# SCH_directMessage_2022-07-24.net
KiCad netlist of a schematic drawn in EasyEDA
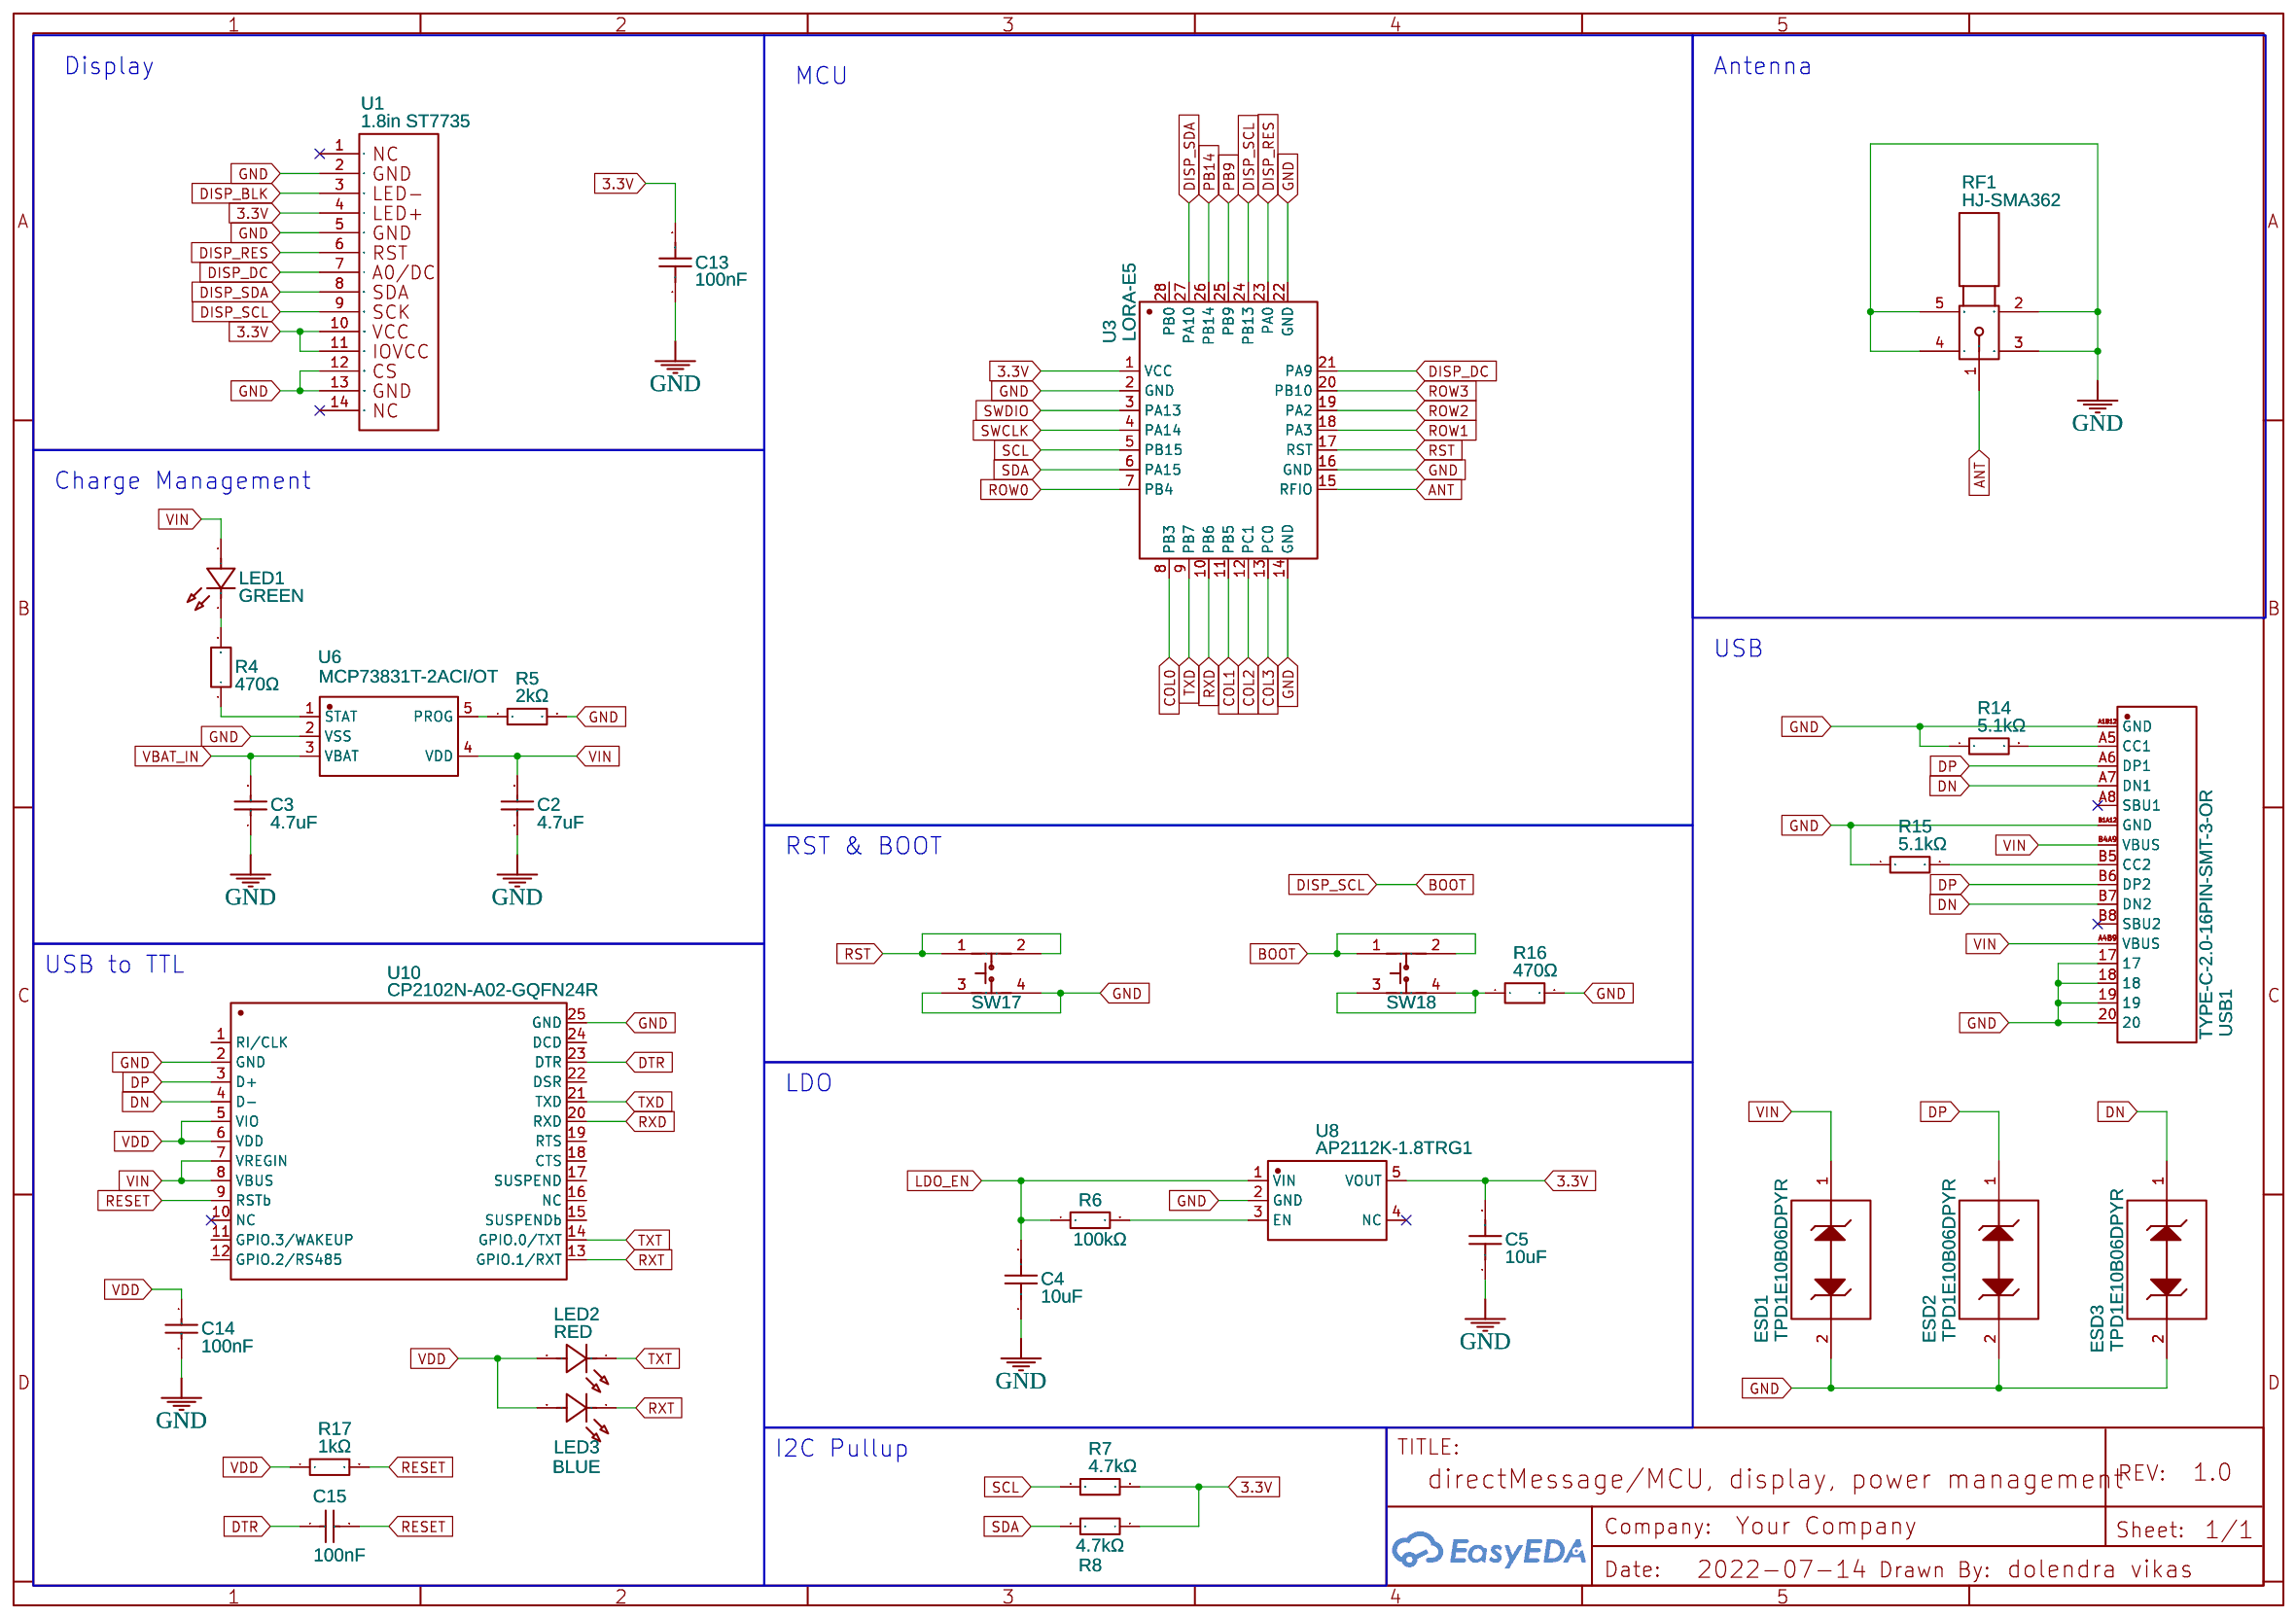
[diagram p0: Sheet_1]
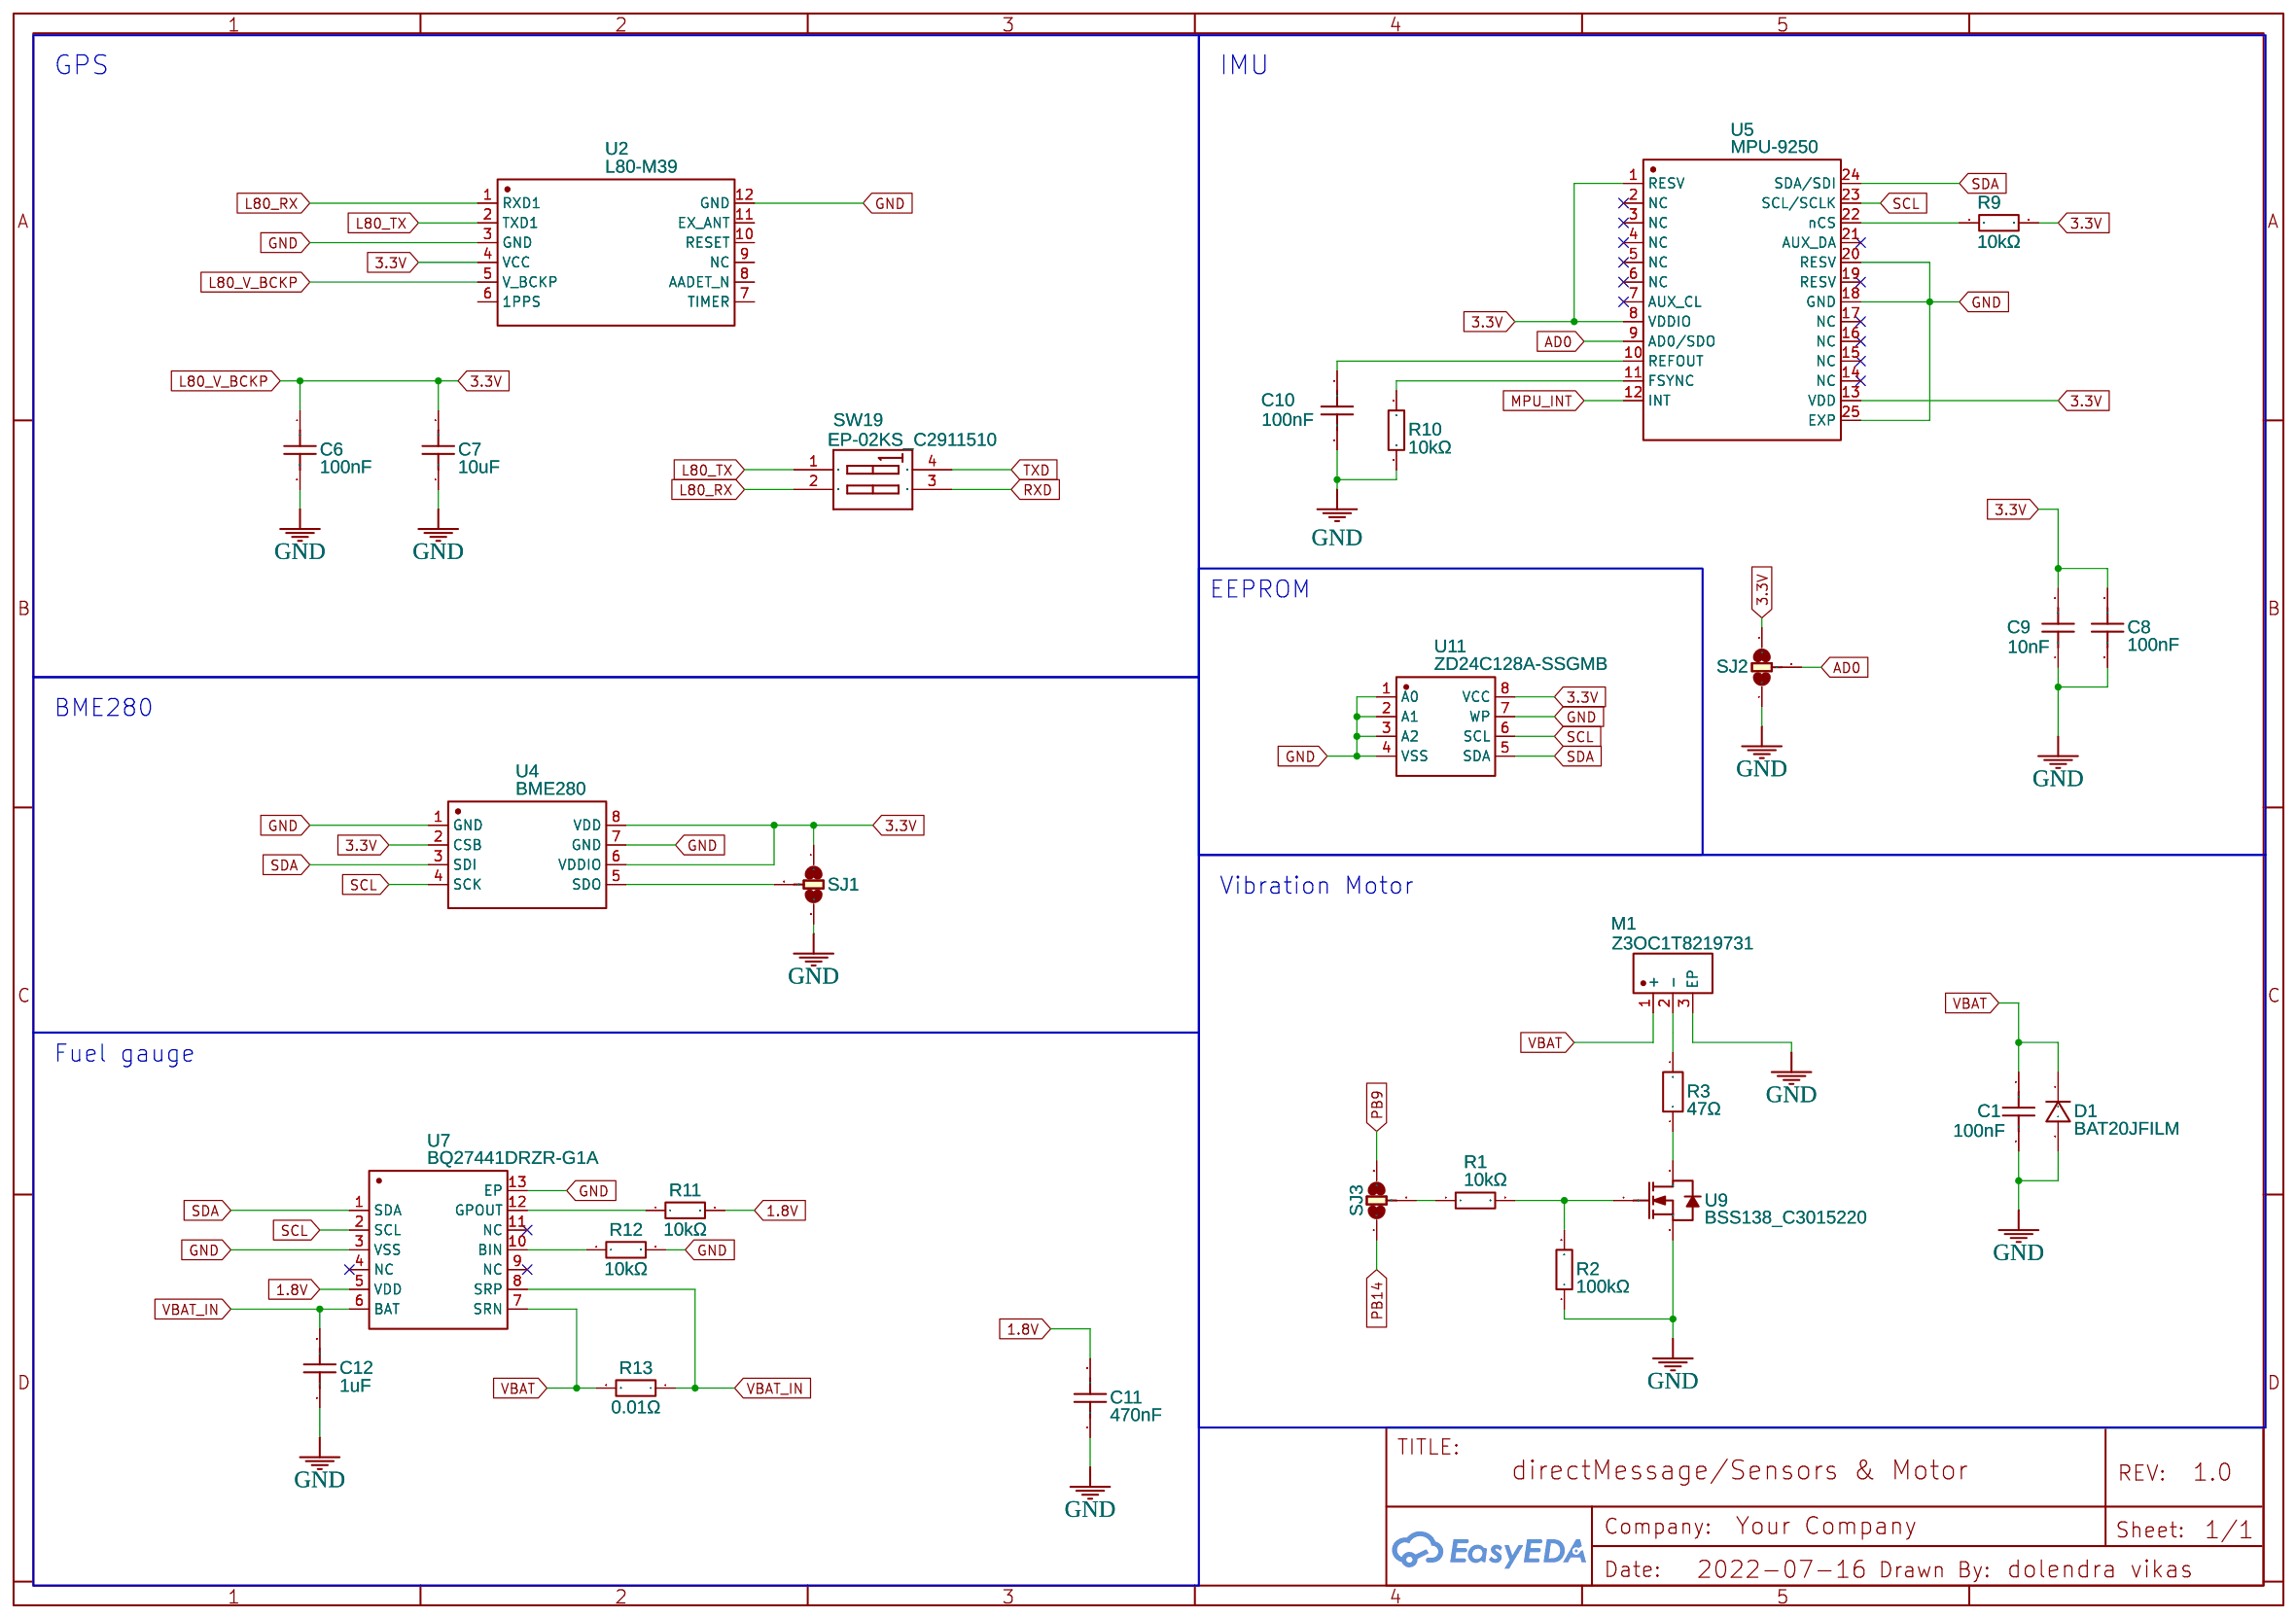
[diagram p1: Sheet_2]
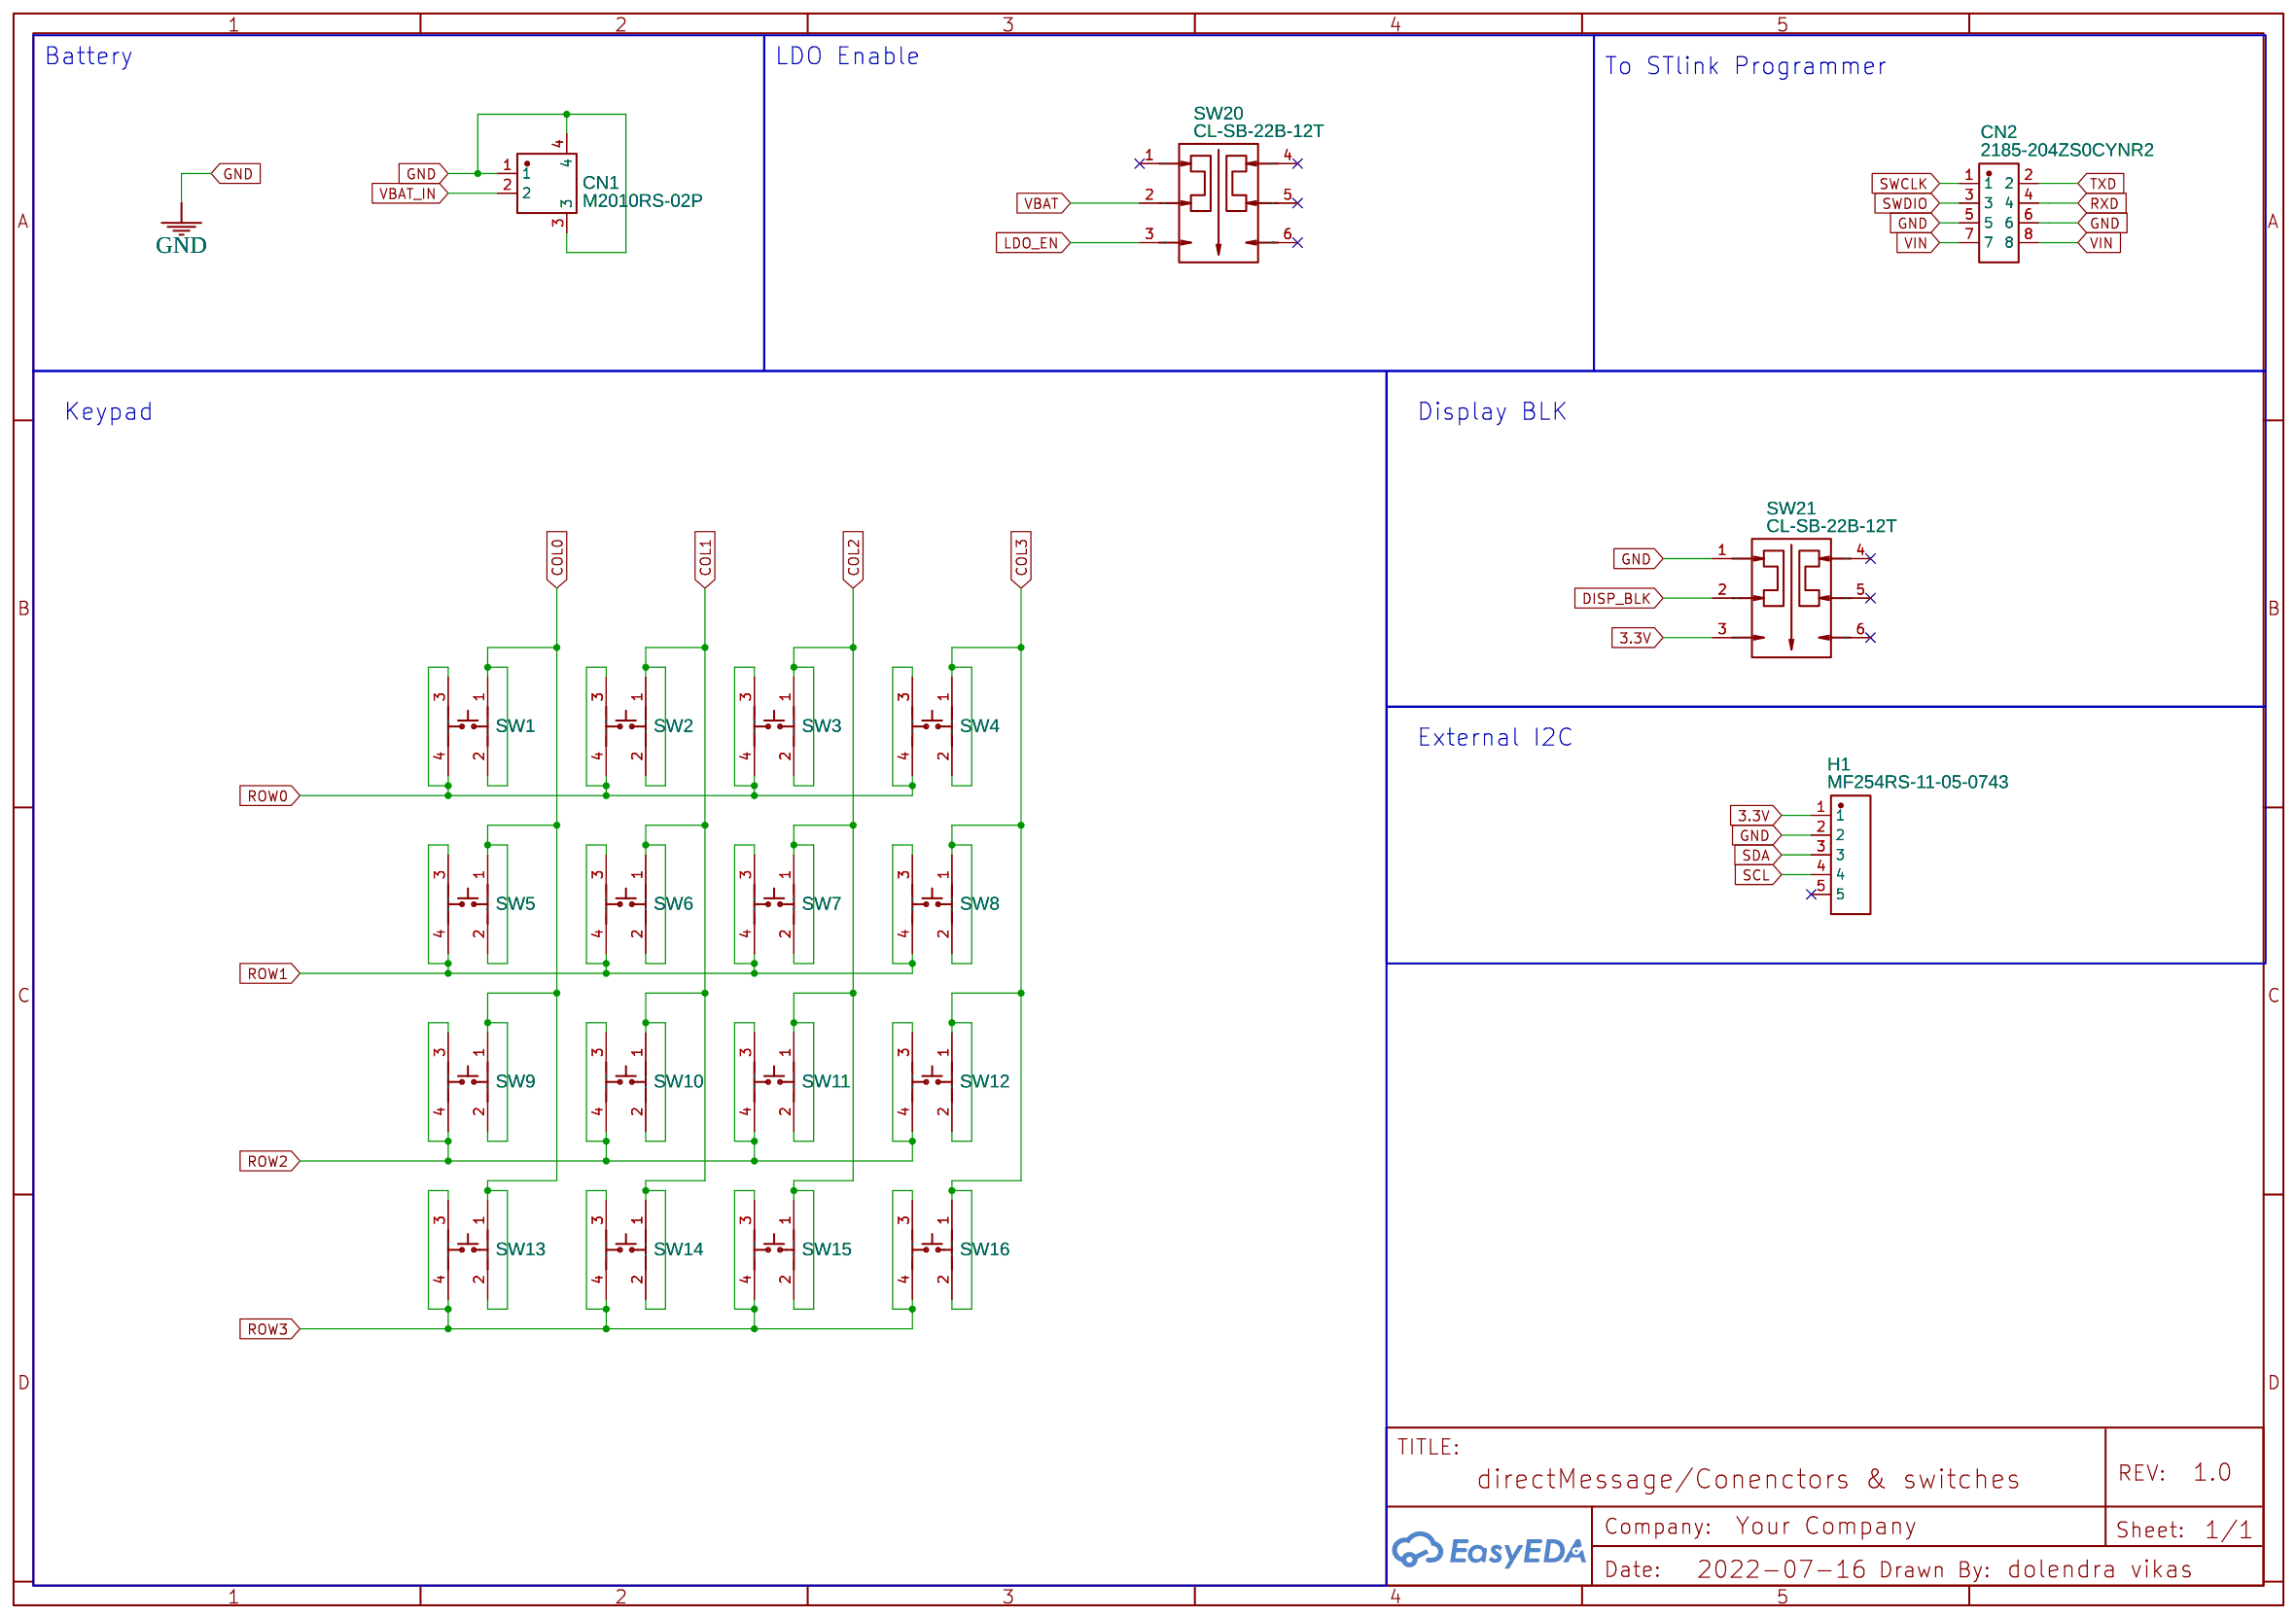
[diagram p2: Sheet_3]

(export (version "E")
  (design (tool "Eeschema 10.0.6"))
  (components
    (comp (ref "C2")
      (value "4.7uF")
      (fields
        (field (name "BOM_Manufacturer Part") "0603F475M100NT")
        (field (name "BOM_Supplier Part") "C108344")
      )
      (libsource (lib "") (part "0603 4.7UF CAPACITOR (SMD)"))
    )
    (comp (ref "C3")
      (value "4.7uF")
      (fields
        (field (name "BOM_Manufacturer Part") "0603F475M100NT")
        (field (name "BOM_Supplier Part") "C108344")
      )
      (libsource (lib "") (part "0603 4.7UF CAPACITOR (SMD)"))
    )
    (comp (ref "C4")
      (value "10uF")
      (fields
        (field (name "BOM_Manufacturer Part") "0603X106M6R3")
        (field (name "BOM_Supplier Part") "C123608")
      )
      (libsource (lib "") (part "0603X106M6R3"))
    )
    (comp (ref "C5")
      (value "10uF")
      (fields
        (field (name "BOM_Manufacturer Part") "0603X106M6R3")
        (field (name "BOM_Supplier Part") "C123608")
      )
      (libsource (lib "") (part "0603X106M6R3"))
    )
    (comp (ref "C13")
      (value "100nF")
      (fields
        (field (name "BOM_Manufacturer Part") "GCM188R71H104KA57D")
        (field (name "BOM_Supplier Part") "C85864")
      )
      (libsource (lib "") (part "GCM188R71H104KA57D"))
    )
    (comp (ref "C14")
      (value "100nF")
      (fields
        (field (name "BOM_Manufacturer Part") "FN18X104K500PBG")
        (field (name "BOM_Supplier Part") "C235731")
      )
      (libsource (lib "") (part "FN18X104K500PBG_1"))
    )
    (comp (ref "C15")
      (value "100nF")
      (fields
        (field (name "BOM_Manufacturer Part") "FN18X104K500PBG")
        (field (name "BOM_Supplier Part") "C235731")
      )
      (libsource (lib "") (part "FN18X104K500PBG"))
    )
    (comp (ref "ESD1")
      (value "TPD1E10B06DPYR")
      (fields (field (name "BOM_Supplier Part") "C48260"))
      (libsource (lib "") (part "TPD1E10B06DPYR"))
    )
    (comp (ref "ESD2")
      (value "TPD1E10B06DPYR")
      (fields (field (name "BOM_Supplier Part") "C48260"))
      (libsource (lib "") (part "TPD1E10B06DPYR"))
    )
    (comp (ref "ESD3")
      (value "TPD1E10B06DPYR")
      (fields (field (name "BOM_Supplier Part") "C48260"))
      (libsource (lib "") (part "TPD1E10B06DPYR"))
    )
    (comp (ref "LED1")
      (value "GREEN")
      (fields
        (field (name "BOM_Manufacturer Part") "XL-1608SYGC-06")
        (field (name "BOM_Supplier Part") "C965805")
      )
      (libsource (lib "") (part "XL-1608SYGC-06"))
    )
    (comp (ref "LED2")
      (value "RED")
      (fields
        (field (name "BOM_Manufacturer Part") "XL-1608SURC-06")
        (field (name "BOM_Supplier Part") "C965799")
      )
      (libsource (lib "") (part "XL-1608SURC-06"))
    )
    (comp (ref "LED3")
      (value "BLUE")
      (fields
        (field (name "BOM_Manufacturer Part") "XL-1608UBC-04")
        (field (name "BOM_Supplier Part") "C965807")
      )
      (libsource (lib "") (part "XL-1608UBC-04"))
    )
    (comp (ref "R4")
      (value "470Ω")
      (fields
        (field (name "BOM_Manufacturer Part") "ERJPA3J471V")
        (field (name "BOM_Supplier Part") "C441888")
      )
      (libsource (lib "") (part "ERJPA3J471V"))
    )
    (comp (ref "R5")
      (value "2kΩ")
      (fields
        (field (name "BOM_Manufacturer Part") "ERJ-3EKF2001V")
        (field (name "BOM_Supplier Part") "C192167")
      )
      (libsource (lib "") (part "ERJ-3EKF2001V"))
    )
    (comp (ref "R6")
      (value "100kΩ")
      (fields
        (field (name "BOM_Manufacturer Part") "ERJ3EKF1003V")
        (field (name "BOM_Supplier Part") "C189597")
      )
      (libsource (lib "") (part "ERJ3EKF1003V"))
    )
    (comp (ref "R7")
      (value "4.7kΩ")
      (fields
        (field (name "BOM_Manufacturer Part") "ERJ-3RBD4701V")
        (field (name "BOM_Supplier Part") "C191778")
      )
      (libsource (lib "") (part "ERJ-3RBD4701V"))
    )
    (comp (ref "R8")
      (value "4.7kΩ")
      (fields
        (field (name "BOM_Manufacturer Part") "ERJ-3RBD4701V")
        (field (name "BOM_Supplier Part") "C191778")
      )
      (libsource (lib "") (part "ERJ-3RBD4701V_1"))
    )
    (comp (ref "R14")
      (value "5.1kΩ")
      (fields
        (field (name "BOM_Manufacturer Part") "ERJ-3RBD5101V")
        (field (name "BOM_Supplier Part") "C191782")
      )
      (libsource (lib "") (part "ERJ-3RBD5101V"))
    )
    (comp (ref "R15")
      (value "5.1kΩ")
      (fields
        (field (name "BOM_Manufacturer Part") "ERJ-3RBD5101V")
        (field (name "BOM_Supplier Part") "C191782")
      )
      (libsource (lib "") (part "ERJ-3RBD5101V"))
    )
    (comp (ref "R16")
      (value "470Ω")
      (fields
        (field (name "BOM_Manufacturer Part") "ERJPA3J471V")
        (field (name "BOM_Supplier Part") "C441888")
      )
      (libsource (lib "") (part "ERJPA3J471V_1"))
    )
    (comp (ref "R17")
      (value "1kΩ")
      (fields
        (field (name "BOM_Manufacturer Part") "ERJ-3EKF1001V")
        (field (name "BOM_Supplier Part") "C118155")
      )
      (libsource (lib "") (part "ERJ-3EKF1001V"))
    )
    (comp (ref "RF1")
      (value "HJ-SMA362")
      (fields (field (name "BOM_Supplier Part") "C2905338"))
      (libsource (lib "") (part "HJ-SMA362"))
    )
    (comp (ref "SW17")
      (value "SKRPABE010")
      (fields (field (name "BOM_Supplier Part") "C115360"))
      (libsource (lib "") (part "SKRPABE010"))
    )
    (comp (ref "SW18")
      (value "SKRPABE010")
      (fields (field (name "BOM_Supplier Part") "C115360"))
      (libsource (lib "") (part "SKRPABE010"))
    )
    (comp (ref "U1") (value "1.8in ST7735") (libsource (lib "") (part "1.8in ST7735")))
    (comp (ref "U3")
      (value "LORA-E5")
      (fields
        (field (name "BOM_Manufacturer Part") "LoRa-E5")
        (field (name "BOM_Supplier Part") "C9900002286")
      )
      (libsource (lib "") (part "LORA-E5"))
    )
    (comp (ref "U6")
      (value "MCP73831T-2ACI/OT")
      (fields (field (name "BOM_Supplier Part") "C424093"))
      (libsource (lib "") (part "MCP73831T-2ACI/OT"))
    )
    (comp (ref "U8")
      (value "AP2112K-1.8TRG1")
      (fields (field (name "BOM_Supplier Part") "C176944"))
      (libsource (lib "") (part "AP2112K-1.8TRG1"))
    )
    (comp (ref "U10")
      (value "CP2102N-A02-GQFN24R")
      (fields (field (name "BOM_Supplier Part") "C969151"))
      (libsource (lib "") (part "CP2102N-A02-GQFN24R"))
    )
    (comp (ref "USB1")
      (value "TYPE-C-2.0-16PIN-SMT-3-OR")
      (fields (field (name "BOM_Supplier Part") "C2987387"))
      (libsource (lib "") (part "TYPE-C-2.0-16PIN-SMT-3-OR"))
    )
    (comp (ref "C1")
      (value "100nF")
      (fields
        (field (name "BOM_Manufacturer Part") "C0603C104J5RAC")
        (field (name "BOM_Supplier Part") "C490602")
      )
      (libsource (lib "") (part "C0603C104J5RAC"))
    )
    (comp (ref "C6")
      (value "100nF")
      (fields
        (field (name "BOM_Manufacturer Part") "C0603C104J5RAC")
        (field (name "BOM_Supplier Part") "C490602")
      )
      (libsource (lib "") (part "C0603C104J5RAC"))
    )
    (comp (ref "C7")
      (value "10uF")
      (fields
        (field (name "BOM_Manufacturer Part") "0603X106M6R3")
        (field (name "BOM_Supplier Part") "C123608")
      )
      (libsource (lib "") (part "0603X106M6R3"))
    )
    (comp (ref "C8")
      (value "100nF")
      (fields
        (field (name "BOM_Manufacturer Part") "C0603C104J5RAC")
        (field (name "BOM_Supplier Part") "C490602")
      )
      (libsource (lib "") (part "C0603C104J5RAC"))
    )
    (comp (ref "C9")
      (value "10nF")
      (fields
        (field (name "BOM_Manufacturer Part") "C0603C103J3GAC7867")
        (field (name "BOM_Supplier Part") "C140951")
      )
      (libsource (lib "") (part "C0603C103J3GAC7867"))
    )
    (comp (ref "C10")
      (value "100nF")
      (fields
        (field (name "BOM_Manufacturer Part") "C0603C104J5RAC")
        (field (name "BOM_Supplier Part") "C490602")
      )
      (libsource (lib "") (part "C0603C104J5RAC"))
    )
    (comp (ref "C11")
      (value "470nF")
      (fields
        (field (name "BOM_Manufacturer Part") "GCM188R71E474KA64D")
        (field (name "BOM_Supplier Part") "C161219")
      )
      (libsource (lib "") (part "GCM188R71E474KA64D"))
    )
    (comp (ref "C12")
      (value "1uF")
      (fields
        (field (name "BOM_Manufacturer Part") "GRM188R61E105KA12D")
        (field (name "BOM_Supplier Part") "C77046")
      )
      (libsource (lib "") (part "GRM188R61E105KA12D"))
    )
    (comp (ref "D1")
      (value "BAT20JFILM")
      (fields (field (name "BOM_Supplier Part") "C155590"))
      (libsource (lib "") (part "BAT20JFILM"))
    )
    (comp (ref "M1")
      (value "Z3OC1T8219731")
      (fields (field (name "BOM_Supplier Part") "C2894731"))
      (libsource (lib "") (part "Z3OC1T8219731"))
    )
    (comp (ref "R1")
      (value "10kΩ")
      (fields
        (field (name "BOM_Manufacturer Part") "ERJ3GEYJ103V")
        (field (name "BOM_Supplier Part") "C169849")
      )
      (libsource (lib "") (part "ERJ3GEYJ103V"))
    )
    (comp (ref "R2")
      (value "100kΩ")
      (fields
        (field (name "BOM_Manufacturer Part") "ERJ3EKF1003V")
        (field (name "BOM_Supplier Part") "C189597")
      )
      (libsource (lib "") (part "ERJ3EKF1003V"))
    )
    (comp (ref "R3")
      (value "47Ω")
      (fields
        (field (name "BOM_Manufacturer Part") "ERJUP3D47R0V")
        (field (name "BOM_Supplier Part") "C491217")
      )
      (libsource (lib "") (part "ERJUP3D47R0V"))
    )
    (comp (ref "R9")
      (value "10kΩ")
      (fields
        (field (name "BOM_Manufacturer Part") "ERJ3GEYJ103V")
        (field (name "BOM_Supplier Part") "C169849")
      )
      (libsource (lib "") (part "ERJ3GEYJ103V"))
    )
    (comp (ref "R10")
      (value "10kΩ")
      (fields
        (field (name "BOM_Manufacturer Part") "ERJ3GEYJ103V")
        (field (name "BOM_Supplier Part") "C169849")
      )
      (libsource (lib "") (part "ERJ3GEYJ103V_1"))
    )
    (comp (ref "R11")
      (value "10kΩ")
      (fields
        (field (name "BOM_Manufacturer Part") "ERJ3GEYJ103V")
        (field (name "BOM_Supplier Part") "C169849")
      )
      (libsource (lib "") (part "ERJ3GEYJ103V"))
    )
    (comp (ref "R12")
      (value "10kΩ")
      (fields
        (field (name "BOM_Manufacturer Part") "ERJ3GEYJ103V")
        (field (name "BOM_Supplier Part") "C169849")
      )
      (libsource (lib "") (part "ERJ3GEYJ103V"))
    )
    (comp (ref "R13")
      (value "0.01Ω")
      (fields
        (field (name "BOM_Manufacturer Part") "RTT03R010FTP")
        (field (name "BOM_Supplier Part") "C158899")
      )
      (libsource (lib "") (part "RTT03R010FTP"))
    )
    (comp (ref "SJ1") (value "SOLDERJUMPER_2WAY-OLDS") (libsource (lib "") (part "SOLDERJUMPER_2WAY-OLDS_1")))
    (comp (ref "SJ2") (value "SOLDERJUMPER_2WAY-OLDS") (libsource (lib "") (part "SOLDERJUMPER_2WAY-OLDS")))
    (comp (ref "SJ3") (value "SOLDERJUMPER_2WAY-OLDS") (libsource (lib "") (part "SOLDERJUMPER_2WAY-OLDS")))
    (comp (ref "SW19")
      (value "EP-02KS_C2911510")
      (fields (field (name "BOM_Manufacturer Part") "EP-02KS") (field (name "BOM_Supplier Part") "C2911510"))
      (libsource (lib "") (part "EP-02KS_C2911510"))
    )
    (comp (ref "U2")
      (value "L80-M39")
      (fields (field (name "BOM_Supplier Part") "C133488"))
      (libsource (lib "") (part "L80-M39"))
    )
    (comp (ref "U4")
      (value "BME280")
      (fields (field (name "BOM_Supplier Part") "C92489"))
      (libsource (lib "") (part "BME280"))
    )
    (comp (ref "U5")
      (value "MPU-9250")
      (fields (field (name "BOM_Supplier Part") "C71459"))
      (libsource (lib "") (part "MPU-9250"))
    )
    (comp (ref "U7")
      (value "BQ27441DRZR-G1A")
      (fields (field (name "BOM_Supplier Part") "C473397"))
      (libsource (lib "") (part "BQ27441DRZR-G1A"))
    )
    (comp (ref "U9")
      (value "BSS138_C3015220")
      (fields (field (name "BOM_Manufacturer Part") "BSS138") (field (name "BOM_Supplier Part") "C3015220"))
      (libsource (lib "") (part "BSS138_C3015220"))
    )
    (comp (ref "U11")
      (value "ZD24C128A-SSGMB")
      (fields (field (name "BOM_Supplier Part") "C918271"))
      (libsource (lib "") (part "ZD24C128A-SSGMB"))
    )
    (comp (ref "CN1")
      (value "M2010RS-02P")
      (fields (field (name "BOM_Supplier Part") "C520130"))
      (libsource (lib "") (part "M2010RS-02P"))
    )
    (comp (ref "CN2")
      (value "2185-204ZS0CYNR2")
      (fields (field (name "BOM_Supplier Part") "C721893"))
      (libsource (lib "") (part "2185-204ZS0CYNR2"))
    )
    (comp (ref "H1")
      (value "MF254RS-11-05-0743")
      (fields (field (name "BOM_Supplier Part") "C668121"))
      (libsource (lib "") (part "MF254RS-11-05-0743"))
    )
    (comp (ref "SW1")
      (value "SKRPABE010")
      (fields (field (name "BOM_Supplier Part") "C115360"))
      (libsource (lib "") (part "SKRPABE010"))
    )
    (comp (ref "SW2")
      (value "SKRPABE010")
      (fields (field (name "BOM_Supplier Part") "C115360"))
      (libsource (lib "") (part "SKRPABE010"))
    )
    (comp (ref "SW3")
      (value "SKRPABE010")
      (fields (field (name "BOM_Supplier Part") "C115360"))
      (libsource (lib "") (part "SKRPABE010"))
    )
    (comp (ref "SW4")
      (value "SKRPABE010")
      (fields (field (name "BOM_Supplier Part") "C115360"))
      (libsource (lib "") (part "SKRPABE010"))
    )
    (comp (ref "SW5")
      (value "SKRPABE010")
      (fields (field (name "BOM_Supplier Part") "C115360"))
      (libsource (lib "") (part "SKRPABE010"))
    )
    (comp (ref "SW6")
      (value "SKRPABE010")
      (fields (field (name "BOM_Supplier Part") "C115360"))
      (libsource (lib "") (part "SKRPABE010"))
    )
    (comp (ref "SW7")
      (value "SKRPABE010")
      (fields (field (name "BOM_Supplier Part") "C115360"))
      (libsource (lib "") (part "SKRPABE010"))
    )
    (comp (ref "SW8")
      (value "SKRPABE010")
      (fields (field (name "BOM_Supplier Part") "C115360"))
      (libsource (lib "") (part "SKRPABE010"))
    )
    (comp (ref "SW9")
      (value "SKRPABE010")
      (fields (field (name "BOM_Supplier Part") "C115360"))
      (libsource (lib "") (part "SKRPABE010"))
    )
    (comp (ref "SW10")
      (value "SKRPABE010")
      (fields (field (name "BOM_Supplier Part") "C115360"))
      (libsource (lib "") (part "SKRPABE010"))
    )
    (comp (ref "SW11")
      (value "SKRPABE010")
      (fields (field (name "BOM_Supplier Part") "C115360"))
      (libsource (lib "") (part "SKRPABE010"))
    )
    (comp (ref "SW12")
      (value "SKRPABE010")
      (fields (field (name "BOM_Supplier Part") "C115360"))
      (libsource (lib "") (part "SKRPABE010"))
    )
    (comp (ref "SW13")
      (value "SKRPABE010")
      (fields (field (name "BOM_Supplier Part") "C115360"))
      (libsource (lib "") (part "SKRPABE010"))
    )
    (comp (ref "SW14")
      (value "SKRPABE010")
      (fields (field (name "BOM_Supplier Part") "C115360"))
      (libsource (lib "") (part "SKRPABE010"))
    )
    (comp (ref "SW15")
      (value "SKRPABE010")
      (fields (field (name "BOM_Supplier Part") "C115360"))
      (libsource (lib "") (part "SKRPABE010"))
    )
    (comp (ref "SW16")
      (value "SKRPABE010")
      (fields (field (name "BOM_Supplier Part") "C115360"))
      (libsource (lib "") (part "SKRPABE010"))
    )
    (comp (ref "SW20")
      (value "CL-SB-22B-12T")
      (fields (field (name "BOM_Supplier Part") "C2921665"))
      (libsource (lib "") (part "CL-SB-22B-12T"))
    )
    (comp (ref "SW21")
      (value "CL-SB-22B-12T")
      (fields (field (name "BOM_Supplier Part") "C2921665"))
      (libsource (lib "") (part "CL-SB-22B-12T"))
    )
  )
  (nets
    (net (code "1") (name "1.8V") (class "Default")
      (node (ref "C11") (pin "2") (pinfunction "2_2") (pintype "unspecified"))
      (node (ref "R11") (pin "2") (pinfunction "2_2") (pintype "unspecified"))
      (node (ref "U7") (pin "5") (pinfunction "VDD_5") (pintype "unspecified"))
    )
    (net (code "2") (name "3.3V") (class "Default")
      (node (ref "C13") (pin "2") (pinfunction "2_2") (pintype "unspecified"))
      (node (ref "C5") (pin "2") (pinfunction "2_2") (pintype "unspecified"))
      (node (ref "C6") (pin "1") (pinfunction "1_1") (pintype "unspecified"))
      (node (ref "C7") (pin "2") (pinfunction "2_2") (pintype "unspecified"))
      (node (ref "C8") (pin "1") (pinfunction "1_1") (pintype "unspecified"))
      (node (ref "C9") (pin "2") (pinfunction "2_2") (pintype "unspecified"))
      (node (ref "H1") (pin "1") (pinfunction "1_1") (pintype "unspecified"))
      (node (ref "R7") (pin "2") (pinfunction "2_2") (pintype "unspecified"))
      (node (ref "R8") (pin "1") (pinfunction "1_1") (pintype "unspecified"))
      (node (ref "R9") (pin "2") (pinfunction "2_2") (pintype "unspecified"))
      (node (ref "SJ1") (pin "1") (pinfunction "1_1") (pintype "unspecified"))
      (node (ref "SJ2") (pin "3") (pinfunction "3_3") (pintype "unspecified"))
      (node (ref "SW21") (pin "3") (pinfunction "3_3") (pintype "unspecified"))
      (node (ref "U1") (pin "10") (pinfunction "10_10") (pintype "unspecified"))
      (node (ref "U1") (pin "11") (pinfunction "11_11") (pintype "unspecified"))
      (node (ref "U1") (pin "4") (pinfunction "4_4") (pintype "unspecified"))
      (node (ref "U11") (pin "8") (pinfunction "VCC_8") (pintype "unspecified"))
      (node (ref "U2") (pin "4") (pinfunction "VCC_4") (pintype "unspecified"))
      (node (ref "U2") (pin "5") (pinfunction "V_BCKP_5") (pintype "unspecified"))
      (node (ref "U3") (pin "1") (pinfunction "VCC_1") (pintype "unspecified"))
      (node (ref "U4") (pin "2") (pinfunction "CSB_2") (pintype "unspecified"))
      (node (ref "U4") (pin "6") (pinfunction "VDDIO_6") (pintype "unspecified"))
      (node (ref "U4") (pin "8") (pinfunction "VDD_8") (pintype "unspecified"))
      (node (ref "U5") (pin "1") (pinfunction "RESV_1") (pintype "unspecified"))
      (node (ref "U5") (pin "13") (pinfunction "VDD_13") (pintype "unspecified"))
      (node (ref "U5") (pin "8") (pinfunction "VDDIO_8") (pintype "unspecified"))
      (node (ref "U8") (pin "5") (pinfunction "VOUT_5") (pintype "unspecified"))
    )
    (net (code "3") (name "AD0") (class "Default")
      (node (ref "SJ2") (pin "2") (pinfunction "2_2") (pintype "unspecified"))
      (node (ref "U5") (pin "9") (pinfunction "AD0/SDO_9") (pintype "unspecified"))
    )
    (net (code "4") (name "ANT") (class "Default")
      (node (ref "RF1") (pin "1") (pinfunction "1_1") (pintype "unspecified"))
      (node (ref "U3") (pin "15") (pinfunction "RFIO_15") (pintype "unspecified"))
    )
    (net (code "5") (name "BOOT") (class "Default")
      (node (ref "SW18") (pin "1") (pinfunction "1_1") (pintype "unspecified"))
      (node (ref "SW18") (pin "2") (pinfunction "2_2") (pintype "unspecified"))
      (node (ref "U1") (pin "9") (pinfunction "9_9") (pintype "unspecified"))
      (node (ref "U3") (pin "24") (pinfunction "PB13_24") (pintype "unspecified"))
    )
    (net (code "6") (name "COL0") (class "Default")
      (node (ref "SW1") (pin "1") (pinfunction "1_1") (pintype "unspecified"))
      (node (ref "SW1") (pin "2") (pinfunction "2_2") (pintype "unspecified"))
      (node (ref "SW13") (pin "1") (pinfunction "1_1") (pintype "unspecified"))
      (node (ref "SW13") (pin "2") (pinfunction "2_2") (pintype "unspecified"))
      (node (ref "SW5") (pin "1") (pinfunction "1_1") (pintype "unspecified"))
      (node (ref "SW5") (pin "2") (pinfunction "2_2") (pintype "unspecified"))
      (node (ref "SW9") (pin "1") (pinfunction "1_1") (pintype "unspecified"))
      (node (ref "SW9") (pin "2") (pinfunction "2_2") (pintype "unspecified"))
      (node (ref "U3") (pin "8") (pinfunction "PB3_8") (pintype "unspecified"))
    )
    (net (code "7") (name "COL1") (class "Default")
      (node (ref "SW10") (pin "1") (pinfunction "1_1") (pintype "unspecified"))
      (node (ref "SW10") (pin "2") (pinfunction "2_2") (pintype "unspecified"))
      (node (ref "SW14") (pin "1") (pinfunction "1_1") (pintype "unspecified"))
      (node (ref "SW14") (pin "2") (pinfunction "2_2") (pintype "unspecified"))
      (node (ref "SW2") (pin "1") (pinfunction "1_1") (pintype "unspecified"))
      (node (ref "SW2") (pin "2") (pinfunction "2_2") (pintype "unspecified"))
      (node (ref "SW6") (pin "1") (pinfunction "1_1") (pintype "unspecified"))
      (node (ref "SW6") (pin "2") (pinfunction "2_2") (pintype "unspecified"))
      (node (ref "U3") (pin "11") (pinfunction "PB5_11") (pintype "unspecified"))
    )
    (net (code "8") (name "COL2") (class "Default")
      (node (ref "SW11") (pin "1") (pinfunction "1_1") (pintype "unspecified"))
      (node (ref "SW11") (pin "2") (pinfunction "2_2") (pintype "unspecified"))
      (node (ref "SW15") (pin "1") (pinfunction "1_1") (pintype "unspecified"))
      (node (ref "SW15") (pin "2") (pinfunction "2_2") (pintype "unspecified"))
      (node (ref "SW3") (pin "1") (pinfunction "1_1") (pintype "unspecified"))
      (node (ref "SW3") (pin "2") (pinfunction "2_2") (pintype "unspecified"))
      (node (ref "SW7") (pin "1") (pinfunction "1_1") (pintype "unspecified"))
      (node (ref "SW7") (pin "2") (pinfunction "2_2") (pintype "unspecified"))
      (node (ref "U3") (pin "12") (pinfunction "PC1_12") (pintype "unspecified"))
    )
    (net (code "9") (name "COL3") (class "Default")
      (node (ref "SW12") (pin "1") (pinfunction "1_1") (pintype "unspecified"))
      (node (ref "SW12") (pin "2") (pinfunction "2_2") (pintype "unspecified"))
      (node (ref "SW16") (pin "1") (pinfunction "1_1") (pintype "unspecified"))
      (node (ref "SW16") (pin "2") (pinfunction "2_2") (pintype "unspecified"))
      (node (ref "SW4") (pin "1") (pinfunction "1_1") (pintype "unspecified"))
      (node (ref "SW4") (pin "2") (pinfunction "2_2") (pintype "unspecified"))
      (node (ref "SW8") (pin "1") (pinfunction "1_1") (pintype "unspecified"))
      (node (ref "SW8") (pin "2") (pinfunction "2_2") (pintype "unspecified"))
      (node (ref "U3") (pin "13") (pinfunction "PC0_13") (pintype "unspecified"))
    )
    (net (code "10") (name "DISP_BLK") (class "Default")
      (node (ref "SW21") (pin "2") (pinfunction "2_2") (pintype "unspecified"))
      (node (ref "U1") (pin "3") (pinfunction "3_3") (pintype "unspecified"))
    )
    (net (code "11") (name "DISP_DC") (class "Default")
      (node (ref "U1") (pin "7") (pinfunction "7_7") (pintype "unspecified"))
      (node (ref "U3") (pin "21") (pinfunction "PA9_21") (pintype "unspecified"))
    )
    (net (code "12") (name "DISP_RES") (class "Default")
      (node (ref "U1") (pin "6") (pinfunction "6_6") (pintype "unspecified"))
      (node (ref "U3") (pin "23") (pinfunction "PA0_23") (pintype "unspecified"))
    )
    (net (code "13") (name "DISP_SDA") (class "Default")
      (node (ref "U1") (pin "8") (pinfunction "8_8") (pintype "unspecified"))
      (node (ref "U3") (pin "27") (pinfunction "PA10_27") (pintype "unspecified"))
    )
    (net (code "14") (name "DN") (class "Default")
      (node (ref "ESD3") (pin "1") (pintype "bidirectional"))
      (node (ref "U10") (pin "4") (pinfunction "D-_4") (pintype "unspecified"))
      (node (ref "USB1") (pin "A7") (pinfunction "DN1_A7") (pintype "unspecified"))
      (node (ref "USB1") (pin "B7") (pinfunction "DN2_B7") (pintype "unspecified"))
    )
    (net (code "15") (name "DP") (class "Default")
      (node (ref "ESD2") (pin "1") (pintype "bidirectional"))
      (node (ref "U10") (pin "3") (pinfunction "D+_3") (pintype "unspecified"))
      (node (ref "USB1") (pin "A6") (pinfunction "DP1_A6") (pintype "unspecified"))
      (node (ref "USB1") (pin "B6") (pinfunction "DP2_B6") (pintype "unspecified"))
    )
    (net (code "16") (name "DTR") (class "Default")
      (node (ref "C15") (pin "1") (pinfunction "1_1") (pintype "input"))
      (node (ref "U10") (pin "23") (pinfunction "DTR_23") (pintype "unspecified"))
    )
    (net (code "17") (name "GND") (class "Default")
      (node (ref "C1") (pin "2") (pinfunction "2_2") (pintype "unspecified"))
      (node (ref "C10") (pin "2") (pinfunction "2_2") (pintype "unspecified"))
      (node (ref "C11") (pin "1") (pinfunction "1_1") (pintype "unspecified"))
      (node (ref "C12") (pin "1") (pinfunction "1_1") (pintype "unspecified"))
      (node (ref "C13") (pin "1") (pinfunction "1_1") (pintype "unspecified"))
      (node (ref "C14") (pin "2") (pinfunction "2_2") (pintype "input"))
      (node (ref "C2") (pin "1") (pinfunction "1_1") (pintype "input"))
      (node (ref "C3") (pin "1") (pinfunction "1_1") (pintype "input"))
      (node (ref "C4") (pin "1") (pinfunction "1_1") (pintype "unspecified"))
      (node (ref "C5") (pin "1") (pinfunction "1_1") (pintype "unspecified"))
      (node (ref "C6") (pin "2") (pinfunction "2_2") (pintype "unspecified"))
      (node (ref "C7") (pin "1") (pinfunction "1_1") (pintype "unspecified"))
      (node (ref "C8") (pin "2") (pinfunction "2_2") (pintype "unspecified"))
      (node (ref "C9") (pin "1") (pinfunction "1_1") (pintype "unspecified"))
      (node (ref "CN1") (pin "1") (pinfunction "1_1") (pintype "unspecified"))
      (node (ref "CN1") (pin "3") (pinfunction "3_3") (pintype "unspecified"))
      (node (ref "CN1") (pin "4") (pinfunction "4_4") (pintype "unspecified"))
      (node (ref "CN2") (pin "5") (pinfunction "5_5") (pintype "unspecified"))
      (node (ref "CN2") (pin "6") (pinfunction "6_6") (pintype "unspecified"))
      (node (ref "D1") (pin "2") (pinfunction "A_2") (pintype "unspecified"))
      (node (ref "ESD1") (pin "2") (pintype "bidirectional"))
      (node (ref "ESD2") (pin "2") (pintype "bidirectional"))
      (node (ref "ESD3") (pin "2") (pintype "bidirectional"))
      (node (ref "H1") (pin "2") (pinfunction "2_2") (pintype "unspecified"))
      (node (ref "M1") (pin "3") (pinfunction "EP_3") (pintype "unspecified"))
      (node (ref "R10") (pin "2") (pinfunction "2_2") (pintype "unspecified"))
      (node (ref "R12") (pin "2") (pinfunction "2_2") (pintype "unspecified"))
      (node (ref "R14") (pin "1") (pinfunction "1_1") (pintype "unspecified"))
      (node (ref "R15") (pin "1") (pinfunction "1_1") (pintype "unspecified"))
      (node (ref "R16") (pin "2") (pinfunction "2_2") (pintype "unspecified"))
      (node (ref "R2") (pin "1") (pinfunction "1_1") (pintype "unspecified"))
      (node (ref "R5") (pin "2") (pinfunction "2_2") (pintype "unspecified"))
      (node (ref "RF1") (pin "2") (pinfunction "2_2") (pintype "unspecified"))
      (node (ref "RF1") (pin "3") (pinfunction "3_3") (pintype "unspecified"))
      (node (ref "RF1") (pin "4") (pinfunction "4_4") (pintype "unspecified"))
      (node (ref "RF1") (pin "5") (pinfunction "5_5") (pintype "unspecified"))
      (node (ref "SJ1") (pin "3") (pinfunction "3_3") (pintype "unspecified"))
      (node (ref "SJ2") (pin "1") (pinfunction "1_1") (pintype "unspecified"))
      (node (ref "SW17") (pin "3") (pinfunction "3_3") (pintype "unspecified"))
      (node (ref "SW17") (pin "4") (pinfunction "4_4") (pintype "unspecified"))
      (node (ref "SW21") (pin "1") (pinfunction "1_1") (pintype "unspecified"))
      (node (ref "U1") (pin "12") (pinfunction "12_12") (pintype "unspecified"))
      (node (ref "U1") (pin "13") (pinfunction "13_13") (pintype "unspecified"))
      (node (ref "U1") (pin "2") (pinfunction "2_2") (pintype "unspecified"))
      (node (ref "U1") (pin "5") (pinfunction "5_5") (pintype "unspecified"))
      (node (ref "U10") (pin "2") (pinfunction "GND_2") (pintype "unspecified"))
      (node (ref "U10") (pin "25") (pinfunction "GND_25") (pintype "unspecified"))
      (node (ref "U11") (pin "1") (pinfunction "A0_1") (pintype "unspecified"))
      (node (ref "U11") (pin "2") (pinfunction "A1_2") (pintype "unspecified"))
      (node (ref "U11") (pin "3") (pinfunction "A2_3") (pintype "unspecified"))
      (node (ref "U11") (pin "4") (pinfunction "VSS_4") (pintype "unspecified"))
      (node (ref "U11") (pin "7") (pinfunction "WP_7") (pintype "unspecified"))
      (node (ref "U2") (pin "12") (pinfunction "GND_12") (pintype "unspecified"))
      (node (ref "U2") (pin "3") (pinfunction "GND_3") (pintype "unspecified"))
      (node (ref "U3") (pin "14") (pinfunction "GND_14") (pintype "unspecified"))
      (node (ref "U3") (pin "16") (pinfunction "GND_16") (pintype "unspecified"))
      (node (ref "U3") (pin "2") (pinfunction "GND_2") (pintype "unspecified"))
      (node (ref "U3") (pin "22") (pinfunction "GND_22") (pintype "unspecified"))
      (node (ref "U4") (pin "1") (pinfunction "GND_1") (pintype "unspecified"))
      (node (ref "U4") (pin "7") (pinfunction "GND_7") (pintype "unspecified"))
      (node (ref "U5") (pin "18") (pinfunction "GND_18") (pintype "unspecified"))
      (node (ref "U5") (pin "20") (pinfunction "RESV_20") (pintype "unspecified"))
      (node (ref "U5") (pin "25") (pinfunction "EXP_25") (pintype "unspecified"))
      (node (ref "U6") (pin "2") (pinfunction "VSS_2") (pintype "unspecified"))
      (node (ref "U7") (pin "13") (pinfunction "EP_13") (pintype "unspecified"))
      (node (ref "U7") (pin "3") (pinfunction "VSS_3") (pintype "unspecified"))
      (node (ref "U8") (pin "2") (pinfunction "GND_2") (pintype "unspecified"))
      (node (ref "U9") (pin "2") (pinfunction "S_2") (pintype "unspecified"))
      (node (ref "USB1") (pin "17") (pinfunction "17_17") (pintype "unspecified"))
      (node (ref "USB1") (pin "18") (pinfunction "18_18") (pintype "unspecified"))
      (node (ref "USB1") (pin "19") (pinfunction "19_19") (pintype "unspecified"))
      (node (ref "USB1") (pin "20") (pinfunction "20_20") (pintype "unspecified"))
      (node (ref "USB1") (pin "A1B12") (pinfunction "GND_A1B12") (pintype "unspecified"))
      (node (ref "USB1") (pin "B1A12") (pinfunction "GND_B1A12") (pintype "unspecified"))
    )
    (net (code "18") (name "L80_RX") (class "Default")
      (node (ref "SW19") (pin "2") (pinfunction "A2_2") (pintype "input"))
      (node (ref "U2") (pin "1") (pinfunction "RXD1_1") (pintype "unspecified"))
    )
    (net (code "19") (name "L80_TX") (class "Default")
      (node (ref "SW19") (pin "1") (pinfunction "A1_1") (pintype "input"))
      (node (ref "U2") (pin "2") (pinfunction "TXD1_2") (pintype "unspecified"))
    )
    (net (code "20") (name "LDO_EN") (class "Default")
      (node (ref "C4") (pin "2") (pinfunction "2_2") (pintype "unspecified"))
      (node (ref "R6") (pin "1") (pinfunction "1_1") (pintype "unspecified"))
      (node (ref "SW20") (pin "3") (pinfunction "3_3") (pintype "unspecified"))
      (node (ref "U8") (pin "1") (pinfunction "VIN_1") (pintype "unspecified"))
    )
    (net (code "21") (name "MPU_INT") (class "Default")
      (node (ref "U5") (pin "12") (pinfunction "INT_12") (pintype "unspecified"))
    )
    (net (code "22") (name "Net-(LED1-K)") (class "Default")
      (node (ref "LED1") (pin "1") (pinfunction "K_1") (pintype "unspecified"))
      (node (ref "R4") (pin "2") (pinfunction "2_2") (pintype "unspecified"))
    )
    (net (code "23") (name "Net-(M1--)") (class "Default")
      (node (ref "M1") (pin "2") (pinfunction "-_2") (pintype "unspecified"))
      (node (ref "R3") (pin "2") (pinfunction "2_2") (pintype "unspecified"))
    )
    (net (code "24") (name "Net-(R1-Pad1)") (class "Default")
      (node (ref "R1") (pin "1") (pinfunction "1_1") (pintype "unspecified"))
      (node (ref "SJ3") (pin "2") (pinfunction "2_2") (pintype "unspecified"))
    )
    (net (code "25") (name "Net-(R16-Pad1)") (class "Default")
      (node (ref "R16") (pin "1") (pinfunction "1_1") (pintype "unspecified"))
      (node (ref "SW18") (pin "3") (pinfunction "3_3") (pintype "unspecified"))
      (node (ref "SW18") (pin "4") (pinfunction "4_4") (pintype "unspecified"))
    )
    (net (code "26") (name "Net-(U4-SDO)") (class "Default")
      (node (ref "SJ1") (pin "2") (pinfunction "2_2") (pintype "unspecified"))
      (node (ref "U4") (pin "5") (pinfunction "SDO_5") (pintype "unspecified"))
    )
    (net (code "27") (name "Net-(U5-FSYNC)") (class "Default")
      (node (ref "R10") (pin "1") (pinfunction "1_1") (pintype "unspecified"))
      (node (ref "U5") (pin "11") (pinfunction "FSYNC_11") (pintype "unspecified"))
    )
    (net (code "28") (name "Net-(U5-REFOUT)") (class "Default")
      (node (ref "C10") (pin "1") (pinfunction "1_1") (pintype "unspecified"))
      (node (ref "U5") (pin "10") (pinfunction "REFOUT_10") (pintype "unspecified"))
    )
    (net (code "29") (name "Net-(U5-nCS)") (class "Default")
      (node (ref "R9") (pin "1") (pinfunction "1_1") (pintype "unspecified"))
      (node (ref "U5") (pin "22") (pinfunction "nCS_22") (pintype "unspecified"))
    )
    (net (code "30") (name "Net-(U6-PROG)") (class "Default")
      (node (ref "R5") (pin "1") (pinfunction "1_1") (pintype "unspecified"))
      (node (ref "U6") (pin "5") (pinfunction "PROG_5") (pintype "unspecified"))
    )
    (net (code "31") (name "Net-(U6-STAT)") (class "Default")
      (node (ref "R4") (pin "1") (pinfunction "1_1") (pintype "unspecified"))
      (node (ref "U6") (pin "1") (pinfunction "STAT_1") (pintype "unspecified"))
    )
    (net (code "32") (name "Net-(U7-BIN)") (class "Default")
      (node (ref "R12") (pin "1") (pinfunction "1_1") (pintype "unspecified"))
      (node (ref "U7") (pin "10") (pinfunction "BIN_10") (pintype "unspecified"))
    )
    (net (code "33") (name "Net-(U7-GPOUT)") (class "Default")
      (node (ref "R11") (pin "1") (pinfunction "1_1") (pintype "unspecified"))
      (node (ref "U7") (pin "12") (pinfunction "GPOUT_12") (pintype "unspecified"))
    )
    (net (code "34") (name "Net-(U8-EN)") (class "Default")
      (node (ref "R6") (pin "2") (pinfunction "2_2") (pintype "unspecified"))
      (node (ref "U8") (pin "3") (pinfunction "EN_3") (pintype "unspecified"))
    )
    (net (code "35") (name "Net-(U9-D)") (class "Default")
      (node (ref "R3") (pin "1") (pinfunction "1_1") (pintype "unspecified"))
      (node (ref "U9") (pin "3") (pinfunction "D_3") (pintype "unspecified"))
    )
    (net (code "36") (name "Net-(U9-G)") (class "Default")
      (node (ref "R1") (pin "2") (pinfunction "2_2") (pintype "unspecified"))
      (node (ref "R2") (pin "2") (pinfunction "2_2") (pintype "unspecified"))
      (node (ref "U9") (pin "1") (pinfunction "G_1") (pintype "unspecified"))
    )
    (net (code "37") (name "Net-(USB1-CC1)") (class "Default")
      (node (ref "R14") (pin "2") (pinfunction "2_2") (pintype "unspecified"))
      (node (ref "USB1") (pin "A5") (pinfunction "CC1_A5") (pintype "unspecified"))
    )
    (net (code "38") (name "Net-(USB1-CC2)") (class "Default")
      (node (ref "R15") (pin "2") (pinfunction "2_2") (pintype "unspecified"))
      (node (ref "USB1") (pin "B5") (pinfunction "CC2_B5") (pintype "unspecified"))
    )
    (net (code "39") (name "PB9") (class "Default")
      (node (ref "SJ3") (pin "3") (pinfunction "3_3") (pintype "unspecified"))
      (node (ref "U3") (pin "25") (pinfunction "PB9_25") (pintype "unspecified"))
    )
    (net (code "40") (name "PB14") (class "Default")
      (node (ref "SJ3") (pin "1") (pinfunction "1_1") (pintype "unspecified"))
      (node (ref "U3") (pin "26") (pinfunction "PB14_26") (pintype "unspecified"))
    )
    (net (code "41") (name "RESET") (class "Default")
      (node (ref "C15") (pin "2") (pinfunction "2_2") (pintype "input"))
      (node (ref "R17") (pin "2") (pinfunction "2_2") (pintype "unspecified"))
      (node (ref "U10") (pin "9") (pinfunction "RSTb_9") (pintype "unspecified"))
    )
    (net (code "42") (name "ROW0") (class "Default")
      (node (ref "SW1") (pin "3") (pinfunction "3_3") (pintype "unspecified"))
      (node (ref "SW1") (pin "4") (pinfunction "4_4") (pintype "unspecified"))
      (node (ref "SW2") (pin "3") (pinfunction "3_3") (pintype "unspecified"))
      (node (ref "SW2") (pin "4") (pinfunction "4_4") (pintype "unspecified"))
      (node (ref "SW3") (pin "3") (pinfunction "3_3") (pintype "unspecified"))
      (node (ref "SW3") (pin "4") (pinfunction "4_4") (pintype "unspecified"))
      (node (ref "SW4") (pin "3") (pinfunction "3_3") (pintype "unspecified"))
      (node (ref "SW4") (pin "4") (pinfunction "4_4") (pintype "unspecified"))
      (node (ref "U3") (pin "7") (pinfunction "PB4_7") (pintype "unspecified"))
    )
    (net (code "43") (name "ROW1") (class "Default")
      (node (ref "SW5") (pin "3") (pinfunction "3_3") (pintype "unspecified"))
      (node (ref "SW5") (pin "4") (pinfunction "4_4") (pintype "unspecified"))
      (node (ref "SW6") (pin "3") (pinfunction "3_3") (pintype "unspecified"))
      (node (ref "SW6") (pin "4") (pinfunction "4_4") (pintype "unspecified"))
      (node (ref "SW7") (pin "3") (pinfunction "3_3") (pintype "unspecified"))
      (node (ref "SW7") (pin "4") (pinfunction "4_4") (pintype "unspecified"))
      (node (ref "SW8") (pin "3") (pinfunction "3_3") (pintype "unspecified"))
      (node (ref "SW8") (pin "4") (pinfunction "4_4") (pintype "unspecified"))
      (node (ref "U3") (pin "18") (pinfunction "PA3_18") (pintype "unspecified"))
    )
    (net (code "44") (name "ROW2") (class "Default")
      (node (ref "SW10") (pin "3") (pinfunction "3_3") (pintype "unspecified"))
      (node (ref "SW10") (pin "4") (pinfunction "4_4") (pintype "unspecified"))
      (node (ref "SW11") (pin "3") (pinfunction "3_3") (pintype "unspecified"))
      (node (ref "SW11") (pin "4") (pinfunction "4_4") (pintype "unspecified"))
      (node (ref "SW12") (pin "3") (pinfunction "3_3") (pintype "unspecified"))
      (node (ref "SW12") (pin "4") (pinfunction "4_4") (pintype "unspecified"))
      (node (ref "SW9") (pin "3") (pinfunction "3_3") (pintype "unspecified"))
      (node (ref "SW9") (pin "4") (pinfunction "4_4") (pintype "unspecified"))
      (node (ref "U3") (pin "19") (pinfunction "PA2_19") (pintype "unspecified"))
    )
    (net (code "45") (name "ROW3") (class "Default")
      (node (ref "SW13") (pin "3") (pinfunction "3_3") (pintype "unspecified"))
      (node (ref "SW13") (pin "4") (pinfunction "4_4") (pintype "unspecified"))
      (node (ref "SW14") (pin "3") (pinfunction "3_3") (pintype "unspecified"))
      (node (ref "SW14") (pin "4") (pinfunction "4_4") (pintype "unspecified"))
      (node (ref "SW15") (pin "3") (pinfunction "3_3") (pintype "unspecified"))
      (node (ref "SW15") (pin "4") (pinfunction "4_4") (pintype "unspecified"))
      (node (ref "SW16") (pin "3") (pinfunction "3_3") (pintype "unspecified"))
      (node (ref "SW16") (pin "4") (pinfunction "4_4") (pintype "unspecified"))
      (node (ref "U3") (pin "20") (pinfunction "PB10_20") (pintype "unspecified"))
    )
    (net (code "46") (name "RST") (class "Default")
      (node (ref "SW17") (pin "1") (pinfunction "1_1") (pintype "unspecified"))
      (node (ref "SW17") (pin "2") (pinfunction "2_2") (pintype "unspecified"))
      (node (ref "U3") (pin "17") (pinfunction "RST_17") (pintype "unspecified"))
    )
    (net (code "47") (name "RXD") (class "Default")
      (node (ref "CN2") (pin "4") (pinfunction "4_4") (pintype "unspecified"))
      (node (ref "SW19") (pin "3") (pinfunction "B2_3") (pintype "input"))
      (node (ref "U10") (pin "20") (pinfunction "RXD_20") (pintype "unspecified"))
      (node (ref "U3") (pin "10") (pinfunction "PB6_10") (pintype "unspecified"))
    )
    (net (code "48") (name "RXT") (class "Default")
      (node (ref "LED3") (pin "1") (pinfunction "K_1") (pintype "unspecified"))
      (node (ref "U10") (pin "13") (pinfunction "GPIO.1/RXT_13") (pintype "unspecified"))
    )
    (net (code "49") (name "SCL") (class "Default")
      (node (ref "H1") (pin "4") (pinfunction "4_4") (pintype "unspecified"))
      (node (ref "R7") (pin "1") (pinfunction "1_1") (pintype "unspecified"))
      (node (ref "U11") (pin "6") (pinfunction "SCL_6") (pintype "unspecified"))
      (node (ref "U3") (pin "5") (pinfunction "PB15_5") (pintype "unspecified"))
      (node (ref "U4") (pin "4") (pinfunction "SCK_4") (pintype "unspecified"))
      (node (ref "U5") (pin "23") (pinfunction "SCL/SCLK_23") (pintype "unspecified"))
      (node (ref "U7") (pin "2") (pinfunction "SCL_2") (pintype "unspecified"))
    )
    (net (code "50") (name "SDA") (class "Default")
      (node (ref "H1") (pin "3") (pinfunction "3_3") (pintype "unspecified"))
      (node (ref "R8") (pin "2") (pinfunction "2_2") (pintype "unspecified"))
      (node (ref "U11") (pin "5") (pinfunction "SDA_5") (pintype "unspecified"))
      (node (ref "U3") (pin "6") (pinfunction "PA15_6") (pintype "unspecified"))
      (node (ref "U4") (pin "3") (pinfunction "SDI_3") (pintype "unspecified"))
      (node (ref "U5") (pin "24") (pinfunction "SDA/SDI_24") (pintype "unspecified"))
      (node (ref "U7") (pin "1") (pinfunction "SDA_1") (pintype "unspecified"))
    )
    (net (code "51") (name "SWCLK") (class "Default")
      (node (ref "CN2") (pin "1") (pinfunction "1_1") (pintype "unspecified"))
      (node (ref "U3") (pin "4") (pinfunction "PA14_4") (pintype "unspecified"))
    )
    (net (code "52") (name "SWDIO") (class "Default")
      (node (ref "CN2") (pin "3") (pinfunction "3_3") (pintype "unspecified"))
      (node (ref "U3") (pin "3") (pinfunction "PA13_3") (pintype "unspecified"))
    )
    (net (code "53") (name "TXD") (class "Default")
      (node (ref "CN2") (pin "2") (pinfunction "2_2") (pintype "unspecified"))
      (node (ref "SW19") (pin "4") (pinfunction "B1_4") (pintype "input"))
      (node (ref "U10") (pin "21") (pinfunction "TXD_21") (pintype "unspecified"))
      (node (ref "U3") (pin "9") (pinfunction "PB7_9") (pintype "unspecified"))
    )
    (net (code "54") (name "TXT") (class "Default")
      (node (ref "LED2") (pin "1") (pinfunction "K_1") (pintype "unspecified"))
      (node (ref "U10") (pin "14") (pinfunction "GPIO.0/TXT_14") (pintype "unspecified"))
    )
    (net (code "55") (name "VBAT") (class "Default")
      (node (ref "C1") (pin "1") (pinfunction "1_1") (pintype "unspecified"))
      (node (ref "D1") (pin "1") (pinfunction "K_1") (pintype "unspecified"))
      (node (ref "M1") (pin "1") (pinfunction "+_1") (pintype "unspecified"))
      (node (ref "R13") (pin "2") (pinfunction "2_2") (pintype "unspecified"))
      (node (ref "SW20") (pin "2") (pinfunction "2_2") (pintype "unspecified"))
      (node (ref "U7") (pin "7") (pinfunction "SRN_7") (pintype "unspecified"))
    )
    (net (code "56") (name "VBAT_IN") (class "Default")
      (node (ref "C12") (pin "2") (pinfunction "2_2") (pintype "unspecified"))
      (node (ref "C3") (pin "2") (pinfunction "2_2") (pintype "input"))
      (node (ref "CN1") (pin "2") (pinfunction "2_2") (pintype "unspecified"))
      (node (ref "R13") (pin "1") (pinfunction "1_1") (pintype "unspecified"))
      (node (ref "U6") (pin "3") (pinfunction "VBAT_3") (pintype "unspecified"))
      (node (ref "U7") (pin "6") (pinfunction "BAT_6") (pintype "unspecified"))
      (node (ref "U7") (pin "8") (pinfunction "SRP_8") (pintype "unspecified"))
    )
    (net (code "57") (name "VDD") (class "Default")
      (node (ref "C14") (pin "1") (pinfunction "1_1") (pintype "input"))
      (node (ref "LED2") (pin "2") (pinfunction "A_2") (pintype "unspecified"))
      (node (ref "LED3") (pin "2") (pinfunction "A_2") (pintype "unspecified"))
      (node (ref "R17") (pin "1") (pinfunction "1_1") (pintype "unspecified"))
      (node (ref "U10") (pin "5") (pinfunction "VIO_5") (pintype "unspecified"))
      (node (ref "U10") (pin "6") (pinfunction "VDD_6") (pintype "unspecified"))
    )
    (net (code "58") (name "VIN") (class "Default")
      (node (ref "C2") (pin "2") (pinfunction "2_2") (pintype "input"))
      (node (ref "CN2") (pin "7") (pinfunction "7_7") (pintype "unspecified"))
      (node (ref "CN2") (pin "8") (pinfunction "8_8") (pintype "unspecified"))
      (node (ref "ESD1") (pin "1") (pintype "bidirectional"))
      (node (ref "LED1") (pin "2") (pinfunction "A_2") (pintype "unspecified"))
      (node (ref "U10") (pin "7") (pinfunction "VREGIN_7") (pintype "unspecified"))
      (node (ref "U10") (pin "8") (pinfunction "VBUS_8") (pintype "unspecified"))
      (node (ref "U6") (pin "4") (pinfunction "VDD_4") (pintype "unspecified"))
      (node (ref "USB1") (pin "A4B9") (pinfunction "VBUS_A4B9") (pintype "unspecified"))
      (node (ref "USB1") (pin "B4A9") (pinfunction "VBUS_B4A9") (pintype "unspecified"))
    )
    (net (code "59") (name "unconnected-(H1-Pad5)") (class "Default")
      (node (ref "H1") (pin "5") (pinfunction "5_5") (pintype "unspecified+no_connect"))
    )
    (net (code "60") (name "unconnected-(SW20-Pad1)") (class "Default")
      (node (ref "SW20") (pin "1") (pinfunction "1_1") (pintype "unspecified+no_connect"))
    )
    (net (code "61") (name "unconnected-(SW20-Pad4)") (class "Default")
      (node (ref "SW20") (pin "4") (pinfunction "4_4") (pintype "unspecified+no_connect"))
    )
    (net (code "62") (name "unconnected-(SW20-Pad5)") (class "Default")
      (node (ref "SW20") (pin "5") (pinfunction "5_5") (pintype "unspecified+no_connect"))
    )
    (net (code "63") (name "unconnected-(SW20-Pad6)") (class "Default")
      (node (ref "SW20") (pin "6") (pinfunction "6_6") (pintype "unspecified+no_connect"))
    )
    (net (code "64") (name "unconnected-(SW21-Pad4)") (class "Default")
      (node (ref "SW21") (pin "4") (pinfunction "4_4") (pintype "unspecified+no_connect"))
    )
    (net (code "65") (name "unconnected-(SW21-Pad5)") (class "Default")
      (node (ref "SW21") (pin "5") (pinfunction "5_5") (pintype "unspecified+no_connect"))
    )
    (net (code "66") (name "unconnected-(SW21-Pad6)") (class "Default")
      (node (ref "SW21") (pin "6") (pinfunction "6_6") (pintype "unspecified+no_connect"))
    )
    (net (code "67") (name "unconnected-(U1-Pad1)") (class "Default")
      (node (ref "U1") (pin "1") (pinfunction "1_1") (pintype "unspecified+no_connect"))
    )
    (net (code "68") (name "unconnected-(U1-Pad14)") (class "Default")
      (node (ref "U1") (pin "14") (pinfunction "14_14") (pintype "unspecified+no_connect"))
    )
    (net (code "69") (name "unconnected-(U2-1PPS-Pad6)") (class "Default")
      (node (ref "U2") (pin "6") (pinfunction "1PPS_6") (pintype "unspecified"))
    )
    (net (code "70") (name "unconnected-(U2-AADET_N-Pad8)") (class "Default")
      (node (ref "U2") (pin "8") (pinfunction "AADET_N_8") (pintype "unspecified"))
    )
    (net (code "71") (name "unconnected-(U2-EX_ANT-Pad11)") (class "Default")
      (node (ref "U2") (pin "11") (pinfunction "EX_ANT_11") (pintype "unspecified"))
    )
    (net (code "72") (name "unconnected-(U2-NC-Pad9)") (class "Default")
      (node (ref "U2") (pin "9") (pinfunction "NC_9") (pintype "unspecified"))
    )
    (net (code "73") (name "unconnected-(U2-RESET-Pad10)") (class "Default")
      (node (ref "U2") (pin "10") (pinfunction "RESET_10") (pintype "unspecified"))
    )
    (net (code "74") (name "unconnected-(U2-TIMER-Pad7)") (class "Default")
      (node (ref "U2") (pin "7") (pinfunction "TIMER_7") (pintype "unspecified"))
    )
    (net (code "75") (name "unconnected-(U3-PB0-Pad28)") (class "Default")
      (node (ref "U3") (pin "28") (pinfunction "PB0_28") (pintype "unspecified"))
    )
    (net (code "76") (name "unconnected-(U5-AUX_CL-Pad7)") (class "Default")
      (node (ref "U5") (pin "7") (pinfunction "AUX_CL_7") (pintype "unspecified+no_connect"))
    )
    (net (code "77") (name "unconnected-(U5-AUX_DA-Pad21)") (class "Default")
      (node (ref "U5") (pin "21") (pinfunction "AUX_DA_21") (pintype "unspecified+no_connect"))
    )
    (net (code "78") (name "unconnected-(U5-NC-Pad2)") (class "Default")
      (node (ref "U5") (pin "2") (pinfunction "NC_2") (pintype "unspecified+no_connect"))
    )
    (net (code "79") (name "unconnected-(U5-NC-Pad3)") (class "Default")
      (node (ref "U5") (pin "3") (pinfunction "NC_3") (pintype "unspecified+no_connect"))
    )
    (net (code "80") (name "unconnected-(U5-NC-Pad4)") (class "Default")
      (node (ref "U5") (pin "4") (pinfunction "NC_4") (pintype "unspecified+no_connect"))
    )
    (net (code "81") (name "unconnected-(U5-NC-Pad5)") (class "Default")
      (node (ref "U5") (pin "5") (pinfunction "NC_5") (pintype "unspecified+no_connect"))
    )
    (net (code "82") (name "unconnected-(U5-NC-Pad6)") (class "Default")
      (node (ref "U5") (pin "6") (pinfunction "NC_6") (pintype "unspecified+no_connect"))
    )
    (net (code "83") (name "unconnected-(U5-NC-Pad14)") (class "Default")
      (node (ref "U5") (pin "14") (pinfunction "NC_14") (pintype "unspecified+no_connect"))
    )
    (net (code "84") (name "unconnected-(U5-NC-Pad15)") (class "Default")
      (node (ref "U5") (pin "15") (pinfunction "NC_15") (pintype "unspecified+no_connect"))
    )
    (net (code "85") (name "unconnected-(U5-NC-Pad16)") (class "Default")
      (node (ref "U5") (pin "16") (pinfunction "NC_16") (pintype "unspecified+no_connect"))
    )
    (net (code "86") (name "unconnected-(U5-NC-Pad17)") (class "Default")
      (node (ref "U5") (pin "17") (pinfunction "NC_17") (pintype "unspecified+no_connect"))
    )
    (net (code "87") (name "unconnected-(U5-RESV-Pad19)") (class "Default")
      (node (ref "U5") (pin "19") (pinfunction "RESV_19") (pintype "unspecified+no_connect"))
    )
    (net (code "88") (name "unconnected-(U7-NC-Pad4)") (class "Default")
      (node (ref "U7") (pin "4") (pinfunction "NC_4") (pintype "unspecified+no_connect"))
    )
    (net (code "89") (name "unconnected-(U7-NC-Pad9)") (class "Default")
      (node (ref "U7") (pin "9") (pinfunction "NC_9") (pintype "unspecified+no_connect"))
    )
    (net (code "90") (name "unconnected-(U7-NC-Pad11)") (class "Default")
      (node (ref "U7") (pin "11") (pinfunction "NC_11") (pintype "unspecified+no_connect"))
    )
    (net (code "91") (name "unconnected-(U8-NC-Pad4)") (class "Default")
      (node (ref "U8") (pin "4") (pinfunction "NC_4") (pintype "unspecified+no_connect"))
    )
    (net (code "92") (name "unconnected-(U10-CTS-Pad18)") (class "Default")
      (node (ref "U10") (pin "18") (pinfunction "CTS_18") (pintype "unspecified"))
    )
    (net (code "93") (name "unconnected-(U10-DCD-Pad24)") (class "Default")
      (node (ref "U10") (pin "24") (pinfunction "DCD_24") (pintype "unspecified"))
    )
    (net (code "94") (name "unconnected-(U10-DSR-Pad22)") (class "Default")
      (node (ref "U10") (pin "22") (pinfunction "DSR_22") (pintype "unspecified"))
    )
    (net (code "95") (name "unconnected-(U10-GPIO.2{slash}RS485-Pad12)") (class "Default")
      (node (ref "U10") (pin "12") (pinfunction "GPIO.2/RS485_12") (pintype "unspecified"))
    )
    (net (code "96") (name "unconnected-(U10-GPIO.3{slash}WAKEUP-Pad11)") (class "Default")
      (node (ref "U10") (pin "11") (pinfunction "GPIO.3/WAKEUP_11") (pintype "unspecified"))
    )
    (net (code "97") (name "unconnected-(U10-NC-Pad10)") (class "Default")
      (node (ref "U10") (pin "10") (pinfunction "NC_10") (pintype "unspecified+no_connect"))
    )
    (net (code "98") (name "unconnected-(U10-NC-Pad16)") (class "Default")
      (node (ref "U10") (pin "16") (pinfunction "NC_16") (pintype "unspecified"))
    )
    (net (code "99") (name "unconnected-(U10-RI{slash}CLK-Pad1)") (class "Default")
      (node (ref "U10") (pin "1") (pinfunction "RI/CLK_1") (pintype "unspecified"))
    )
    (net (code "100") (name "unconnected-(U10-RTS-Pad19)") (class "Default")
      (node (ref "U10") (pin "19") (pinfunction "RTS_19") (pintype "unspecified"))
    )
    (net (code "101") (name "unconnected-(U10-SUSPEND-Pad17)") (class "Default")
      (node (ref "U10") (pin "17") (pinfunction "SUSPEND_17") (pintype "unspecified"))
    )
    (net (code "102") (name "unconnected-(U10-SUSPENDb-Pad15)") (class "Default")
      (node (ref "U10") (pin "15") (pinfunction "SUSPENDb_15") (pintype "unspecified"))
    )
    (net (code "103") (name "unconnected-(USB1-SBU1-PadA8)") (class "Default")
      (node (ref "USB1") (pin "A8") (pinfunction "SBU1_A8") (pintype "unspecified+no_connect"))
    )
    (net (code "104") (name "unconnected-(USB1-SBU2-PadB8)") (class "Default")
      (node (ref "USB1") (pin "B8") (pinfunction "SBU2_B8") (pintype "unspecified+no_connect"))
    )
  )
)
